# 1.net
KiCad netlist of a schematic drawn in EAGLE
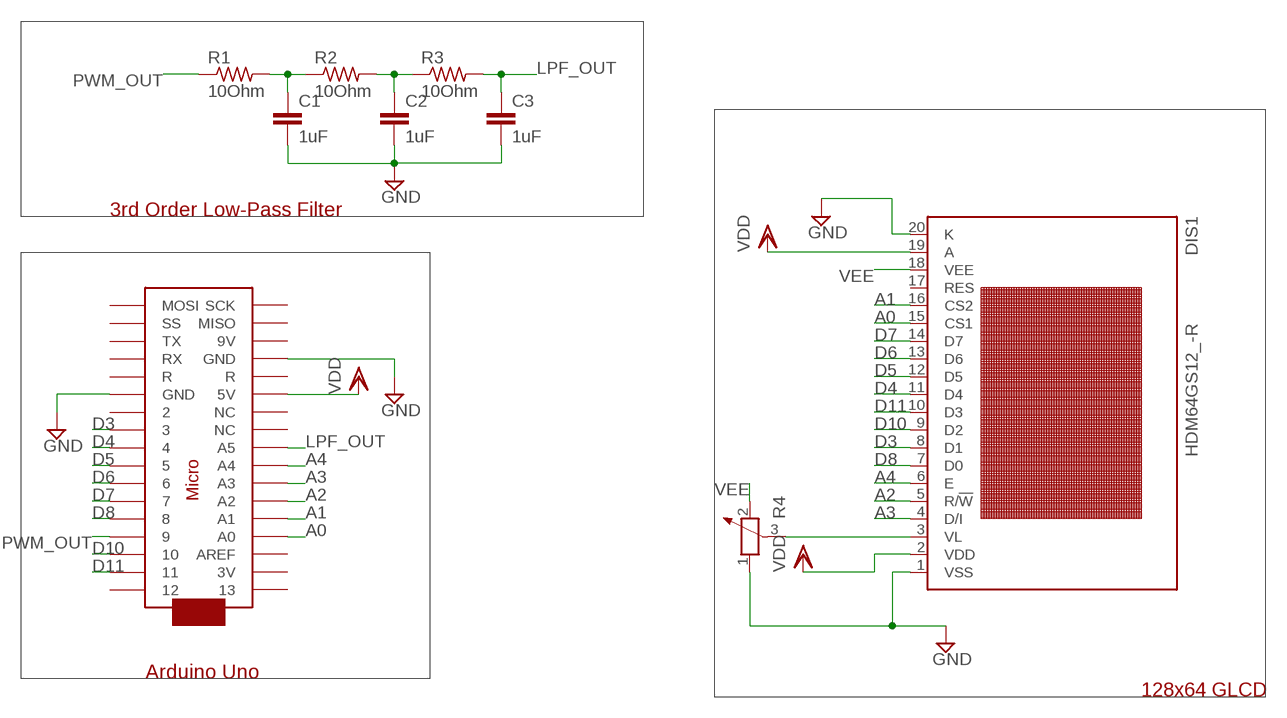
[diagram p0: schematic, sheet 1]

(export (version "E")
  (design (tool "Eeschema 10.0.6"))
  (components
    (comp (ref "C1")
      (value "1uF")
      (footprint "eagle-import:C025-030X050")
      (libsource (lib "eagle-import") (part "C-EU025-030X050"))
    )
    (comp (ref "C2")
      (value "1uF")
      (footprint "eagle-import:C025-030X050")
      (libsource (lib "eagle-import") (part "C-EU025-030X050"))
    )
    (comp (ref "C3")
      (value "1uF")
      (footprint "eagle-import:C025-030X050")
      (libsource (lib "eagle-import") (part "C-EU025-030X050"))
    )
    (comp (ref "DIS1")
      (value "HDM64GS12_-R")
      (footprint "eagle-import:HDM64GS12_-R")
      (libsource (lib "eagle-import") (part "HDM64GS12_-R"))
    )
    (comp (ref "R1")
      (value "10Ohm")
      (footprint "eagle-import:0204_7")
      (libsource (lib "eagle-import") (part "R-US_0204/7"))
    )
    (comp (ref "R2")
      (value "10Ohm")
      (footprint "eagle-import:0204_7")
      (libsource (lib "eagle-import") (part "R-US_0204/7"))
    )
    (comp (ref "R3")
      (value "10Ohm")
      (footprint "eagle-import:0204_7")
      (libsource (lib "eagle-import") (part "R-US_0204/7"))
    )
    (comp (ref "R4")
      (value "POTENTIOMETER_PT-10")
      (footprint "eagle-import:PT-10")
      (libsource (lib "eagle-import") (part "POTENTIOMETER_PT-10"))
    )
    (comp (ref "U$1")
      (value "Arduino")
      (footprint "eagle-import:ARDUINOMICRO")
      (libsource (lib "eagle-import") (part "ARDUINOMICRO"))
    )
  )
  (nets
    (net (code "1") (name "/A0") (class "Default")
      (node (ref "DIS1") (pin "15") (pinfunction "CS1_15") (pintype "input"))
      (node (ref "U$1") (pin "P$31") (pinfunction "A0_P$31") (pintype "bidirectional"))
    )
    (net (code "2") (name "/A1") (class "Default")
      (node (ref "DIS1") (pin "16") (pinfunction "CS2_16") (pintype "input"))
      (node (ref "U$1") (pin "P$30") (pinfunction "A1_P$30") (pintype "bidirectional"))
    )
    (net (code "3") (name "/A2") (class "Default")
      (node (ref "DIS1") (pin "5") (pinfunction "R/~{W}_5") (pintype "input"))
      (node (ref "U$1") (pin "P$29") (pinfunction "A2_P$29") (pintype "bidirectional"))
    )
    (net (code "4") (name "/A3") (class "Default")
      (node (ref "DIS1") (pin "4") (pinfunction "D/I_4") (pintype "input"))
      (node (ref "U$1") (pin "P$28") (pinfunction "A3_P$28") (pintype "bidirectional"))
    )
    (net (code "5") (name "/A4") (class "Default")
      (node (ref "DIS1") (pin "6") (pinfunction "E_6") (pintype "input"))
      (node (ref "U$1") (pin "P$27") (pinfunction "A4_P$27") (pintype "bidirectional"))
    )
    (net (code "6") (name "/D3") (class "Default")
      (node (ref "DIS1") (pin "8") (pinfunction "D1_8") (pintype "bidirectional"))
      (node (ref "U$1") (pin "P$10") (pinfunction "3_P$10") (pintype "bidirectional"))
    )
    (net (code "7") (name "/D4") (class "Default")
      (node (ref "DIS1") (pin "11") (pinfunction "D4_11") (pintype "bidirectional"))
      (node (ref "U$1") (pin "P$9") (pinfunction "4_P$9") (pintype "bidirectional"))
    )
    (net (code "8") (name "/D5") (class "Default")
      (node (ref "DIS1") (pin "12") (pinfunction "D5_12") (pintype "bidirectional"))
      (node (ref "U$1") (pin "P$8") (pinfunction "5_P$8") (pintype "bidirectional"))
    )
    (net (code "9") (name "/D6") (class "Default")
      (node (ref "DIS1") (pin "13") (pinfunction "D6_13") (pintype "bidirectional"))
      (node (ref "U$1") (pin "P$7") (pinfunction "6_P$7") (pintype "bidirectional"))
    )
    (net (code "10") (name "/D7") (class "Default")
      (node (ref "DIS1") (pin "14") (pinfunction "D7_14") (pintype "bidirectional"))
      (node (ref "U$1") (pin "P$6") (pinfunction "7_P$6") (pintype "bidirectional"))
    )
    (net (code "11") (name "/D8") (class "Default")
      (node (ref "DIS1") (pin "7") (pinfunction "D0_7") (pintype "bidirectional"))
      (node (ref "U$1") (pin "P$5") (pinfunction "8_P$5") (pintype "bidirectional"))
    )
    (net (code "12") (name "/D10") (class "Default")
      (node (ref "DIS1") (pin "9") (pinfunction "D2_9") (pintype "bidirectional"))
      (node (ref "U$1") (pin "P$3") (pinfunction "10_P$3") (pintype "bidirectional"))
    )
    (net (code "13") (name "/D11") (class "Default")
      (node (ref "DIS1") (pin "10") (pinfunction "D3_10") (pintype "bidirectional"))
      (node (ref "U$1") (pin "P$2") (pinfunction "11_P$2") (pintype "bidirectional"))
    )
    (net (code "14") (name "/LPF_OUT") (class "Default")
      (node (ref "C3") (pin "1") (pinfunction "1_1") (pintype "passive"))
      (node (ref "R3") (pin "2") (pinfunction "2_2") (pintype "passive"))
      (node (ref "U$1") (pin "P$26") (pinfunction "A5_P$26") (pintype "bidirectional"))
    )
    (net (code "15") (name "/PWM_OUT") (class "Default")
      (node (ref "R1") (pin "1") (pinfunction "1_1") (pintype "passive"))
      (node (ref "U$1") (pin "P$4") (pinfunction "9_P$4") (pintype "bidirectional"))
    )
    (net (code "16") (name "/VEE") (class "Default")
      (node (ref "DIS1") (pin "18") (pinfunction "VEE_18") (pintype "output"))
      (node (ref "R4") (pin "2") (pinfunction "2_2") (pintype "passive"))
    )
    (net (code "17") (name "GND") (class "Default")
      (node (ref "C1") (pin "2") (pinfunction "2_2") (pintype "passive"))
      (node (ref "C2") (pin "2") (pinfunction "2_2") (pintype "passive"))
      (node (ref "C3") (pin "2") (pinfunction "2_2") (pintype "passive"))
      (node (ref "DIS1") (pin "1") (pinfunction "VSS_1") (pintype "power_in"))
      (node (ref "DIS1") (pin "20") (pinfunction "K_20") (pintype "passive"))
      (node (ref "R4") (pin "1") (pinfunction "1_1") (pintype "passive"))
      (node (ref "U$1") (pin "P$12") (pinfunction "GND_P$12") (pintype "bidirectional"))
      (node (ref "U$1") (pin "P$21") (pinfunction "GND_P$21") (pintype "bidirectional"))
    )
    (net (code "18") (name "Net-(C1-Pad1)") (class "Default")
      (node (ref "C1") (pin "1") (pinfunction "1_1") (pintype "passive"))
      (node (ref "R1") (pin "2") (pinfunction "2_2") (pintype "passive"))
      (node (ref "R2") (pin "1") (pinfunction "1_1") (pintype "passive"))
    )
    (net (code "19") (name "Net-(C2-Pad1)") (class "Default")
      (node (ref "C2") (pin "1") (pinfunction "1_1") (pintype "passive"))
      (node (ref "R2") (pin "2") (pinfunction "2_2") (pintype "passive"))
      (node (ref "R3") (pin "1") (pinfunction "1_1") (pintype "passive"))
    )
    (net (code "20") (name "Net-(DIS1-VL)") (class "Default")
      (node (ref "DIS1") (pin "3") (pinfunction "VL_3") (pintype "passive"))
      (node (ref "R4") (pin "3") (pinfunction "3_3") (pintype "passive"))
    )
    (net (code "21") (name "VDD") (class "Default")
      (node (ref "DIS1") (pin "19") (pinfunction "A_19") (pintype "passive"))
      (node (ref "DIS1") (pin "2") (pinfunction "VDD_2") (pintype "power_in"))
      (node (ref "U$1") (pin "P$23") (pinfunction "5V_P$23") (pintype "bidirectional"))
    )
    (net (code "22") (name "unconnected-(DIS1-RES-Pad17)") (class "Default")
      (node (ref "DIS1") (pin "17") (pinfunction "RES_17") (pintype "input"))
    )
    (net (code "23") (name "unconnected-(U$1-2-PadP$11)") (class "Default")
      (node (ref "U$1") (pin "P$11") (pinfunction "2_P$11") (pintype "bidirectional"))
    )
    (net (code "24") (name "unconnected-(U$1-3V-PadP$33)") (class "Default")
      (node (ref "U$1") (pin "P$33") (pinfunction "3V_P$33") (pintype "bidirectional"))
    )
    (net (code "25") (name "unconnected-(U$1-9V-PadP$20)") (class "Default")
      (node (ref "U$1") (pin "P$20") (pinfunction "9V_P$20") (pintype "bidirectional"))
    )
    (net (code "26") (name "unconnected-(U$1-12-PadP$1)") (class "Default")
      (node (ref "U$1") (pin "P$1") (pinfunction "12_P$1") (pintype "bidirectional"))
    )
    (net (code "27") (name "unconnected-(U$1-13-PadP$34)") (class "Default")
      (node (ref "U$1") (pin "P$34") (pinfunction "13_P$34") (pintype "bidirectional"))
    )
    (net (code "28") (name "unconnected-(U$1-AREF-PadP$32)") (class "Default")
      (node (ref "U$1") (pin "P$32") (pinfunction "AREF_P$32") (pintype "bidirectional"))
    )
    (net (code "29") (name "unconnected-(U$1-MISO-PadP$19)") (class "Default")
      (node (ref "U$1") (pin "P$19") (pinfunction "MISO_P$19") (pintype "bidirectional"))
    )
    (net (code "30") (name "unconnected-(U$1-MOSI-PadP$17)") (class "Default")
      (node (ref "U$1") (pin "P$17") (pinfunction "MOSI_P$17") (pintype "bidirectional"))
    )
    (net (code "31") (name "unconnected-(U$1-NC-PadP$24)") (class "Default")
      (node (ref "U$1") (pin "P$24") (pinfunction "NC_P$24") (pintype "bidirectional"))
    )
    (net (code "32") (name "unconnected-(U$1-NC-PadP$25)") (class "Default")
      (node (ref "U$1") (pin "P$25") (pinfunction "NC_P$25") (pintype "bidirectional"))
    )
    (net (code "33") (name "unconnected-(U$1-R-PadP$13)") (class "Default")
      (node (ref "U$1") (pin "P$13") (pinfunction "R_P$13") (pintype "bidirectional"))
    )
    (net (code "34") (name "unconnected-(U$1-R-PadP$22)") (class "Default")
      (node (ref "U$1") (pin "P$22") (pinfunction "R_P$22") (pintype "bidirectional"))
    )
    (net (code "35") (name "unconnected-(U$1-RX-PadP$14)") (class "Default")
      (node (ref "U$1") (pin "P$14") (pinfunction "RX_P$14") (pintype "bidirectional"))
    )
    (net (code "36") (name "unconnected-(U$1-SCK-PadP$18)") (class "Default")
      (node (ref "U$1") (pin "P$18") (pinfunction "SCK_P$18") (pintype "bidirectional"))
    )
    (net (code "37") (name "unconnected-(U$1-SS-PadP$16)") (class "Default")
      (node (ref "U$1") (pin "P$16") (pinfunction "SS_P$16") (pintype "bidirectional"))
    )
    (net (code "38") (name "unconnected-(U$1-TX-PadP$15)") (class "Default")
      (node (ref "U$1") (pin "P$15") (pinfunction "TX_P$15") (pintype "bidirectional"))
    )
  )
)
